# AVerCADE_Dip_SF.net
KiCad netlist of a schematic drawn in EAGLE
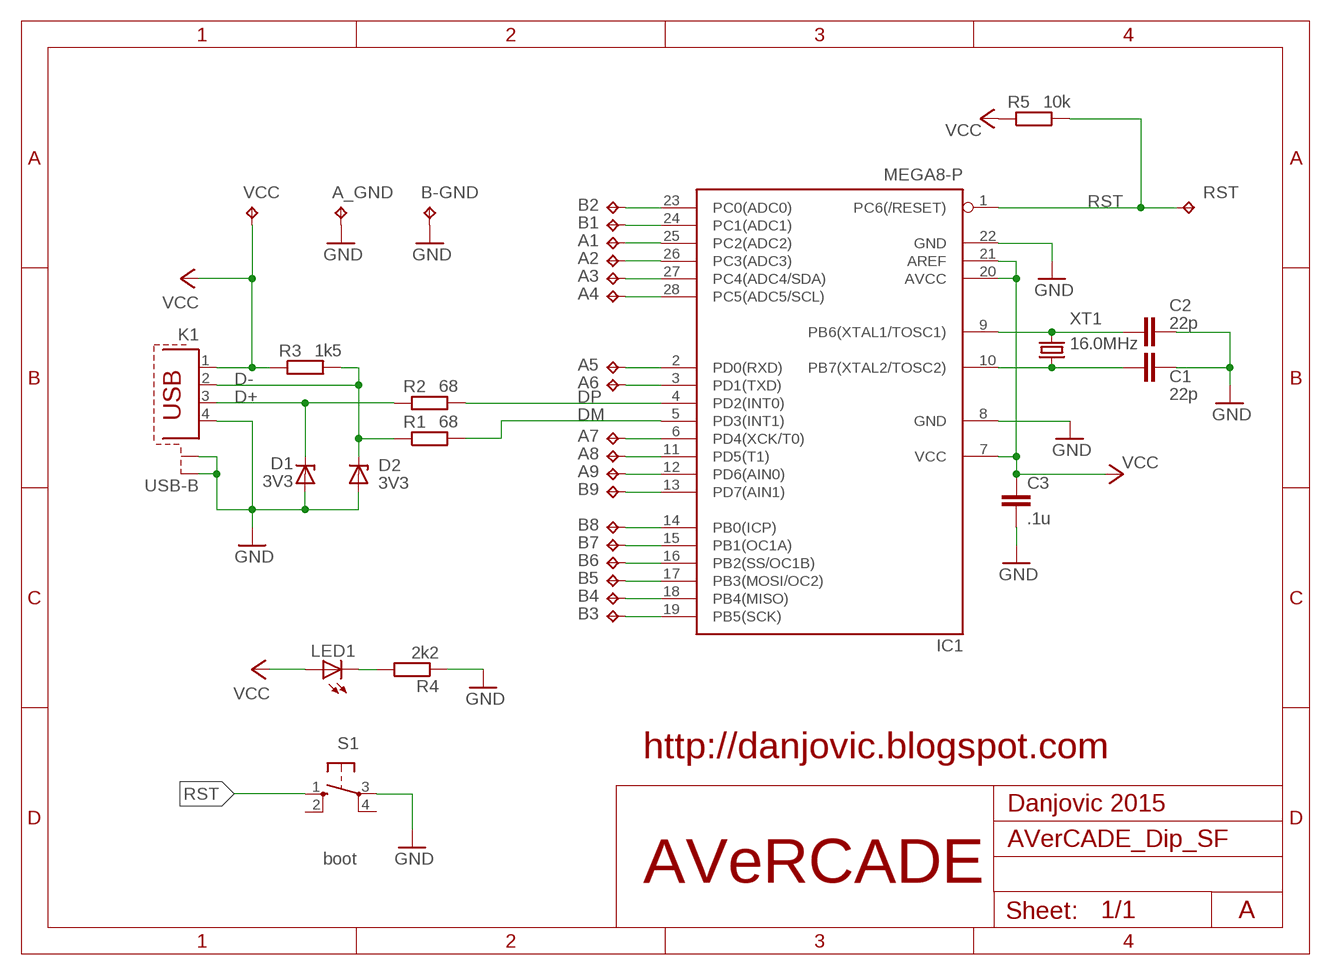
[diagram p0: schematic, sheet 1]

(export (version "E")
  (design (tool "Eeschema 10.0.6"))
  (components
    (comp (ref "A1")
      (value "TPPAD1-13")
      (footprint "eagle-import:P1-13")
      (libsource (lib "eagle-import") (part "TPPAD1-13"))
    )
    (comp (ref "A2")
      (value "TPPAD1-13")
      (footprint "eagle-import:P1-13")
      (libsource (lib "eagle-import") (part "TPPAD1-13"))
    )
    (comp (ref "A3")
      (value "TPPAD1-13")
      (footprint "eagle-import:P1-13")
      (libsource (lib "eagle-import") (part "TPPAD1-13"))
    )
    (comp (ref "A4")
      (value "TPPAD1-13")
      (footprint "eagle-import:P1-13")
      (libsource (lib "eagle-import") (part "TPPAD1-13"))
    )
    (comp (ref "A5")
      (value "TPPAD1-13")
      (footprint "eagle-import:P1-13")
      (libsource (lib "eagle-import") (part "TPPAD1-13"))
    )
    (comp (ref "A6")
      (value "TPPAD1-13")
      (footprint "eagle-import:P1-13")
      (libsource (lib "eagle-import") (part "TPPAD1-13"))
    )
    (comp (ref "A7")
      (value "TPPAD1-13")
      (footprint "eagle-import:P1-13")
      (libsource (lib "eagle-import") (part "TPPAD1-13"))
    )
    (comp (ref "A8")
      (value "TPPAD1-13")
      (footprint "eagle-import:P1-13")
      (libsource (lib "eagle-import") (part "TPPAD1-13"))
    )
    (comp (ref "A9")
      (value "TPPAD1-13")
      (footprint "eagle-import:P1-13")
      (libsource (lib "eagle-import") (part "TPPAD1-13"))
    )
    (comp (ref "A_GND")
      (value "TPPAD1-13")
      (footprint "eagle-import:P1-13")
      (libsource (lib "eagle-import") (part "TPPAD1-13"))
    )
    (comp (ref "B-GND")
      (value "TPPAD1-13")
      (footprint "eagle-import:P1-13")
      (libsource (lib "eagle-import") (part "TPPAD1-13"))
    )
    (comp (ref "B1")
      (value "TPPAD1-13")
      (footprint "eagle-import:P1-13")
      (libsource (lib "eagle-import") (part "TPPAD1-13"))
    )
    (comp (ref "B2")
      (value "TPPAD1-13")
      (footprint "eagle-import:P1-13")
      (libsource (lib "eagle-import") (part "TPPAD1-13"))
    )
    (comp (ref "B3")
      (value "TPPAD1-13")
      (footprint "eagle-import:P1-13")
      (libsource (lib "eagle-import") (part "TPPAD1-13"))
    )
    (comp (ref "B4")
      (value "TPPAD1-13")
      (footprint "eagle-import:P1-13")
      (libsource (lib "eagle-import") (part "TPPAD1-13"))
    )
    (comp (ref "B5")
      (value "TPPAD1-13")
      (footprint "eagle-import:P1-13")
      (libsource (lib "eagle-import") (part "TPPAD1-13"))
    )
    (comp (ref "B6")
      (value "TPPAD1-13")
      (footprint "eagle-import:P1-13")
      (libsource (lib "eagle-import") (part "TPPAD1-13"))
    )
    (comp (ref "B7")
      (value "TPPAD1-13")
      (footprint "eagle-import:P1-13")
      (libsource (lib "eagle-import") (part "TPPAD1-13"))
    )
    (comp (ref "B8")
      (value "TPPAD1-13")
      (footprint "eagle-import:P1-13")
      (libsource (lib "eagle-import") (part "TPPAD1-13"))
    )
    (comp (ref "B9")
      (value "TPPAD1-13")
      (footprint "eagle-import:P1-13")
      (libsource (lib "eagle-import") (part "TPPAD1-13"))
    )
    (comp (ref "C1")
      (value "22p")
      (footprint "eagle-import:C025-24X044L")
      (libsource (lib "eagle-import") (part "C-EUC025-24X044L"))
    )
    (comp (ref "C2")
      (value "22p")
      (footprint "eagle-import:C025-24X044L")
      (libsource (lib "eagle-import") (part "C-EUC025-24X044L"))
    )
    (comp (ref "C3")
      (value ".1u")
      (footprint "eagle-import:C050-025X075L")
      (libsource (lib "eagle-import") (part "C-EUC050-025X075L"))
    )
    (comp (ref "D1")
      (value "3V3")
      (footprint "eagle-import:ZDIO-5L")
      (libsource (lib "eagle-import") (part "ZENER-DIODEZDIO-5L"))
    )
    (comp (ref "D2")
      (value "3V3")
      (footprint "eagle-import:ZDIO-5L")
      (libsource (lib "eagle-import") (part "ZENER-DIODEZDIO-5L"))
    )
    (comp (ref "IC1")
      (value "MEGA8-P")
      (footprint "eagle-import:DIL28-3")
      (libsource (lib "eagle-import") (part "MEGA8-P"))
    )
    (comp (ref "K1")
      (value "USB-B")
      (footprint "eagle-import:PN61729-SL")
      (libsource (lib "eagle-import") (part "PN61729-SPN61729-SL"))
    )
    (comp (ref "LED1")
      (value "LEDLED3MML")
      (footprint "eagle-import:LED3MML")
      (libsource (lib "eagle-import") (part "LEDLED3MML"))
    )
    (comp (ref "R1")
      (value "68")
      (footprint "eagle-import:0207_7L")
      (libsource (lib "eagle-import") (part "R-EU_0207/7L"))
    )
    (comp (ref "R2")
      (value "68")
      (footprint "eagle-import:0207_7L")
      (libsource (lib "eagle-import") (part "R-EU_0207/7L"))
    )
    (comp (ref "R3")
      (value "1k5")
      (footprint "eagle-import:0207_7L")
      (libsource (lib "eagle-import") (part "R-EU_0207/7L"))
    )
    (comp (ref "R4")
      (value "2k2")
      (footprint "eagle-import:0207_7L")
      (libsource (lib "eagle-import") (part "R-EU_0207/7L"))
    )
    (comp (ref "R5")
      (value "10k")
      (footprint "eagle-import:0207_7L")
      (libsource (lib "eagle-import") (part "R-EU_0207/7L"))
    )
    (comp (ref "RST")
      (value "TPPAD1-13")
      (footprint "eagle-import:P1-13")
      (libsource (lib "eagle-import") (part "TPPAD1-13"))
    )
    (comp (ref "S1")
      (value "10-XX")
      (footprint "eagle-import:B3F-10XX")
      (fields (field (name "MPN") "B3F-1000"))
      (libsource (lib "eagle-import") (part "10-XX"))
    )
    (comp (ref "VCC")
      (value "TPPAD1-13")
      (footprint "eagle-import:P1-13")
      (libsource (lib "eagle-import") (part "TPPAD1-13"))
    )
    (comp (ref "XT1")
      (value "16.0MHz")
      (footprint "eagle-import:HC49U-V")
      (libsource (lib "eagle-import") (part "CRYSTALHC49U-V"))
    )
  )
  (nets
    (net (code "1") (name "/D+") (class "Default")
      (node (ref "D1") (pin "C") (pinfunction "C_C") (pintype "passive"))
      (node (ref "K1") (pin "3") (pinfunction "3_3") (pintype "passive"))
      (node (ref "R2") (pin "3") (pinfunction "1_3") (pintype "passive"))
    )
    (net (code "2") (name "/D-") (class "Default")
      (node (ref "D2") (pin "C") (pinfunction "C_C") (pintype "passive"))
      (node (ref "K1") (pin "2") (pinfunction "2_2") (pintype "passive"))
      (node (ref "R1") (pin "3") (pinfunction "1_3") (pintype "passive"))
      (node (ref "R3") (pin "4") (pinfunction "2_4") (pintype "passive"))
    )
    (net (code "3") (name "/DM") (class "Default")
      (node (ref "IC1") (pin "5") (pinfunction "PD3(INT1)_5") (pintype "bidirectional"))
      (node (ref "R1") (pin "4") (pinfunction "2_4") (pintype "passive"))
    )
    (net (code "4") (name "/DP") (class "Default")
      (node (ref "IC1") (pin "4") (pinfunction "PD2(INT0)_4") (pintype "bidirectional"))
      (node (ref "R2") (pin "4") (pinfunction "2_4") (pintype "passive"))
    )
    (net (code "5") (name "GND") (class "Default")
      (node (ref "A_GND") (pin "TP") (pinfunction "TP_TP") (pintype "input"))
      (node (ref "B-GND") (pin "TP") (pinfunction "TP_TP") (pintype "input"))
      (node (ref "C1") (pin "2") (pinfunction "2_2") (pintype "passive"))
      (node (ref "C2") (pin "2") (pinfunction "2_2") (pintype "passive"))
      (node (ref "C3") (pin "2") (pinfunction "2_2") (pintype "passive"))
      (node (ref "D1") (pin "A") (pinfunction "A_A") (pintype "passive"))
      (node (ref "D2") (pin "A") (pinfunction "A_A") (pintype "passive"))
      (node (ref "IC1") (pin "22") (pinfunction "GND_22") (pintype "power_in"))
      (node (ref "IC1") (pin "8") (pinfunction "GND_8") (pintype "power_in"))
      (node (ref "K1") (pin "4") (pinfunction "4_4") (pintype "passive"))
      (node (ref "K1") (pin "S1") (pinfunction "S1_S1") (pintype "passive"))
      (node (ref "K1") (pin "S2") (pinfunction "S2_S2") (pintype "passive"))
      (node (ref "R4") (pin "3") (pinfunction "1_3") (pintype "passive"))
      (node (ref "S1") (pin "3") (pinfunction "P_3") (pintype "passive"))
    )
    (net (code "6") (name "Net-(IC1-PB0(ICP))") (class "Default")
      (node (ref "B8") (pin "TP") (pinfunction "TP_TP") (pintype "input"))
      (node (ref "IC1") (pin "14") (pinfunction "PB0(ICP)_14") (pintype "bidirectional"))
    )
    (net (code "7") (name "Net-(IC1-PB1(OC1A))") (class "Default")
      (node (ref "B7") (pin "TP") (pinfunction "TP_TP") (pintype "input"))
      (node (ref "IC1") (pin "15") (pinfunction "PB1(OC1A)_15") (pintype "bidirectional"))
    )
    (net (code "8") (name "Net-(IC1-PB2(SS{slash}OC1B))") (class "Default")
      (node (ref "B6") (pin "TP") (pinfunction "TP_TP") (pintype "input"))
      (node (ref "IC1") (pin "16") (pinfunction "PB2(SS/OC1B)_16") (pintype "bidirectional"))
    )
    (net (code "9") (name "Net-(IC1-PB3(MOSI{slash}OC2))") (class "Default")
      (node (ref "B5") (pin "TP") (pinfunction "TP_TP") (pintype "input"))
      (node (ref "IC1") (pin "17") (pinfunction "PB3(MOSI/OC2)_17") (pintype "bidirectional"))
    )
    (net (code "10") (name "Net-(IC1-PB4(MISO))") (class "Default")
      (node (ref "B4") (pin "TP") (pinfunction "TP_TP") (pintype "input"))
      (node (ref "IC1") (pin "18") (pinfunction "PB4(MISO)_18") (pintype "bidirectional"))
    )
    (net (code "11") (name "Net-(IC1-PB5(SCK))") (class "Default")
      (node (ref "B3") (pin "TP") (pinfunction "TP_TP") (pintype "input"))
      (node (ref "IC1") (pin "19") (pinfunction "PB5(SCK)_19") (pintype "bidirectional"))
    )
    (net (code "12") (name "Net-(IC1-PB6(XTAL1{slash}TOSC1))") (class "Default")
      (node (ref "C2") (pin "1") (pinfunction "1_1") (pintype "passive"))
      (node (ref "IC1") (pin "9") (pinfunction "PB6(XTAL1/TOSC1)_9") (pintype "bidirectional"))
      (node (ref "XT1") (pin "2") (pinfunction "2_2") (pintype "passive"))
    )
    (net (code "13") (name "Net-(IC1-PB7(XTAL2{slash}TOSC2))") (class "Default")
      (node (ref "C1") (pin "1") (pinfunction "1_1") (pintype "passive"))
      (node (ref "IC1") (pin "10") (pinfunction "PB7(XTAL2/TOSC2)_10") (pintype "bidirectional"))
      (node (ref "XT1") (pin "1") (pinfunction "1_1") (pintype "passive"))
    )
    (net (code "14") (name "Net-(IC1-PC0(ADC0))") (class "Default")
      (node (ref "B2") (pin "TP") (pinfunction "TP_TP") (pintype "input"))
      (node (ref "IC1") (pin "23") (pinfunction "PC0(ADC0)_23") (pintype "bidirectional"))
    )
    (net (code "15") (name "Net-(IC1-PC1(ADC1))") (class "Default")
      (node (ref "B1") (pin "TP") (pinfunction "TP_TP") (pintype "input"))
      (node (ref "IC1") (pin "24") (pinfunction "PC1(ADC1)_24") (pintype "bidirectional"))
    )
    (net (code "16") (name "Net-(IC1-PC2(ADC2))") (class "Default")
      (node (ref "A1") (pin "TP") (pinfunction "TP_TP") (pintype "input"))
      (node (ref "IC1") (pin "25") (pinfunction "PC2(ADC2)_25") (pintype "bidirectional"))
    )
    (net (code "17") (name "Net-(IC1-PC3(ADC3))") (class "Default")
      (node (ref "A2") (pin "TP") (pinfunction "TP_TP") (pintype "input"))
      (node (ref "IC1") (pin "26") (pinfunction "PC3(ADC3)_26") (pintype "bidirectional"))
    )
    (net (code "18") (name "Net-(IC1-PC4(ADC4{slash}SDA))") (class "Default")
      (node (ref "A3") (pin "TP") (pinfunction "TP_TP") (pintype "input"))
      (node (ref "IC1") (pin "27") (pinfunction "PC4(ADC4/SDA)_27") (pintype "bidirectional"))
    )
    (net (code "19") (name "Net-(IC1-PC5(ADC5{slash}SCL))") (class "Default")
      (node (ref "A4") (pin "TP") (pinfunction "TP_TP") (pintype "input"))
      (node (ref "IC1") (pin "28") (pinfunction "PC5(ADC5/SCL)_28") (pintype "bidirectional"))
    )
    (net (code "20") (name "Net-(IC1-PD0(RXD))") (class "Default")
      (node (ref "A5") (pin "TP") (pinfunction "TP_TP") (pintype "input"))
      (node (ref "IC1") (pin "2") (pinfunction "PD0(RXD)_2") (pintype "bidirectional"))
    )
    (net (code "21") (name "Net-(IC1-PD1(TXD))") (class "Default")
      (node (ref "A6") (pin "TP") (pinfunction "TP_TP") (pintype "input"))
      (node (ref "IC1") (pin "3") (pinfunction "PD1(TXD)_3") (pintype "bidirectional"))
    )
    (net (code "22") (name "Net-(IC1-PD4(XCK{slash}T0))") (class "Default")
      (node (ref "A7") (pin "TP") (pinfunction "TP_TP") (pintype "input"))
      (node (ref "IC1") (pin "6") (pinfunction "PD4(XCK/T0)_6") (pintype "bidirectional"))
    )
    (net (code "23") (name "Net-(IC1-PD5(T1))") (class "Default")
      (node (ref "A8") (pin "TP") (pinfunction "TP_TP") (pintype "input"))
      (node (ref "IC1") (pin "11") (pinfunction "PD5(T1)_11") (pintype "bidirectional"))
    )
    (net (code "24") (name "Net-(IC1-PD6(AIN0))") (class "Default")
      (node (ref "A9") (pin "TP") (pinfunction "TP_TP") (pintype "input"))
      (node (ref "IC1") (pin "12") (pinfunction "PD6(AIN0)_12") (pintype "bidirectional"))
    )
    (net (code "25") (name "Net-(IC1-PD7(AIN1))") (class "Default")
      (node (ref "B9") (pin "TP") (pinfunction "TP_TP") (pintype "input"))
      (node (ref "IC1") (pin "13") (pinfunction "PD7(AIN1)_13") (pintype "bidirectional"))
    )
    (net (code "26") (name "Net-(LED1-C)") (class "Default")
      (node (ref "LED1") (pin "K") (pinfunction "C_K") (pintype "passive"))
      (node (ref "R4") (pin "4") (pinfunction "2_4") (pintype "passive"))
    )
    (net (code "27") (name "RST") (class "Default")
      (node (ref "IC1") (pin "1") (pinfunction "PC6(/RESET)_1") (pintype "bidirectional"))
      (node (ref "R5") (pin "4") (pinfunction "2_4") (pintype "passive"))
      (node (ref "RST") (pin "TP") (pinfunction "TP_TP") (pintype "input"))
      (node (ref "S1") (pin "1") (pinfunction "S_1") (pintype "passive"))
    )
    (net (code "28") (name "VCC") (class "Default")
      (node (ref "C3") (pin "1") (pinfunction "1_1") (pintype "passive"))
      (node (ref "IC1") (pin "20") (pinfunction "AVCC_20") (pintype "power_in"))
      (node (ref "IC1") (pin "21") (pinfunction "AREF_21") (pintype "passive"))
      (node (ref "IC1") (pin "7") (pinfunction "VCC_7") (pintype "power_in"))
      (node (ref "K1") (pin "1") (pinfunction "1_1") (pintype "passive"))
      (node (ref "LED1") (pin "A") (pinfunction "A_A") (pintype "passive"))
      (node (ref "R3") (pin "3") (pinfunction "1_3") (pintype "passive"))
      (node (ref "R5") (pin "3") (pinfunction "1_3") (pintype "passive"))
      (node (ref "VCC") (pin "TP") (pinfunction "TP_TP") (pintype "input"))
    )
    (net (code "29") (name "unconnected-(S1-P1-Pad4)") (class "Default")
      (node (ref "S1") (pin "4") (pinfunction "P1_4") (pintype "passive"))
    )
    (net (code "30") (name "unconnected-(S1-S1-Pad2)") (class "Default")
      (node (ref "S1") (pin "2") (pinfunction "S1_2") (pintype "passive"))
    )
  )
)
